# mini_BGM111.net
KiCad netlist of a schematic drawn in EAGLE
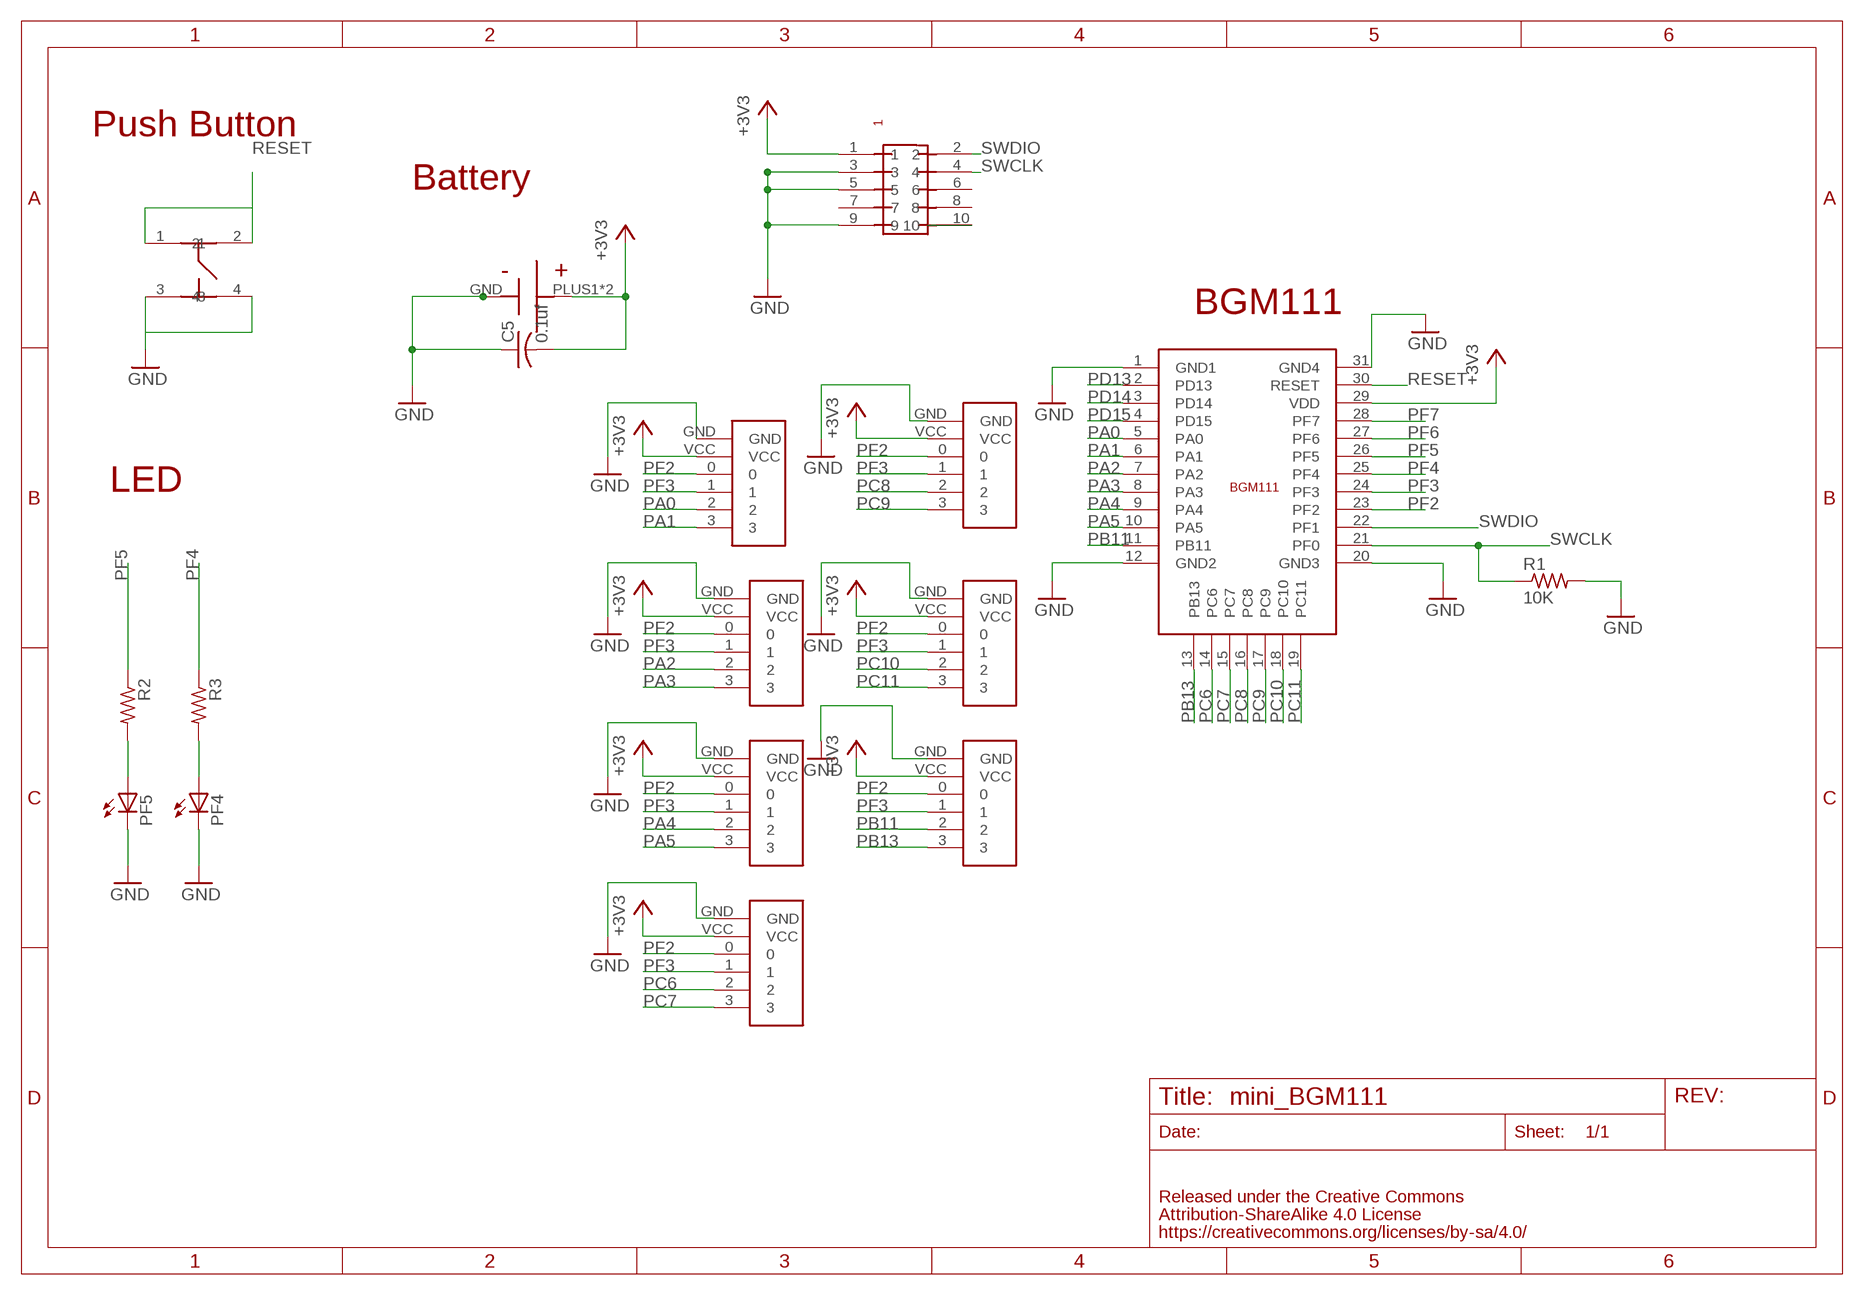
[diagram p0: schematic, sheet 1]

(export (version "E")
  (design (tool "Eeschema 10.0.6"))
  (components
    (comp (ref "C5")
      (value "0.1uf")
      (footprint "eagle-import:C0603")
      (libsource (lib "eagle-import") (part "C-USC0603"))
    )
    (comp (ref "PF4")
      (value "LEDCHIP-LED0603")
      (footprint "eagle-import:CHIP-LED0603")
      (libsource (lib "eagle-import") (part "LEDCHIP-LED0603"))
    )
    (comp (ref "PF5")
      (value "LEDCHIP-LED0603")
      (footprint "eagle-import:CHIP-LED0603")
      (libsource (lib "eagle-import") (part "LEDCHIP-LED0603"))
    )
    (comp (ref "R1")
      (value "10K")
      (footprint "eagle-import:R0603")
      (libsource (lib "eagle-import") (part "R-US_R0603"))
    )
    (comp (ref "R2")
      (value "R-US_R0603")
      (footprint "eagle-import:R0603")
      (libsource (lib "eagle-import") (part "R-US_R0603"))
    )
    (comp (ref "R3")
      (value "R-US_R0603")
      (footprint "eagle-import:R0603")
      (libsource (lib "eagle-import") (part "R-US_R0603"))
    )
    (comp (ref "U$1")
      (value "SILICONLABS-BGM111")
      (footprint "eagle-import:SILICONLABS-BGM111")
      (libsource (lib "eagle-import") (part "SILICONLABS-BGM111"))
    )
    (comp (ref "U$2")
      (value "FABO-PIN-HEADER-2X3-SMD")
      (footprint "eagle-import:FABO-PIN-HEADER-2X3-SMD")
      (libsource (lib "eagle-import") (part "FABO-PIN-HEADER-2X3-SMD"))
    )
    (comp (ref "U$3")
      (value "FABO-PIN-HEADER-2X3-SMD")
      (footprint "eagle-import:FABO-PIN-HEADER-2X3-SMD")
      (libsource (lib "eagle-import") (part "FABO-PIN-HEADER-2X3-SMD"))
    )
    (comp (ref "U$4")
      (value "PIN-HEADER-SMT(1.27MM)2X5")
      (footprint "eagle-import:PIN-HEADER-SMT(1.27MM)2X5")
      (libsource (lib "eagle-import") (part "PIN-HEADER-SMT(1.27MM)2X5"))
    )
    (comp (ref "U$5")
      (value "SWICTH-4P(KMR2)")
      (footprint "eagle-import:SWITCH-4P(KMR2)")
      (libsource (lib "eagle-import") (part "SWICTH-4P(KMR2)"))
    )
    (comp (ref "U$7")
      (value "FABO-PIN-HEADER-2X3-SMD")
      (footprint "eagle-import:FABO-PIN-HEADER-2X3-SMD")
      (libsource (lib "eagle-import") (part "FABO-PIN-HEADER-2X3-SMD"))
    )
    (comp (ref "U$8")
      (value "FABO-PIN-HEADER-2X3-SMD")
      (footprint "eagle-import:FABO-PIN-HEADER-2X3-SMD")
      (libsource (lib "eagle-import") (part "FABO-PIN-HEADER-2X3-SMD"))
    )
    (comp (ref "U$9")
      (value "FABO-PIN-HEADER-2X3-SMD")
      (footprint "eagle-import:FABO-PIN-HEADER-2X3-SMD")
      (libsource (lib "eagle-import") (part "FABO-PIN-HEADER-2X3-SMD"))
    )
    (comp (ref "U$10")
      (value "FABO-PIN-HEADER-2X3-SMD")
      (footprint "eagle-import:FABO-PIN-HEADER-2X3-SMD")
      (libsource (lib "eagle-import") (part "FABO-PIN-HEADER-2X3-SMD"))
    )
    (comp (ref "U$11")
      (value "FABO-PIN-HEADER-2X3-SMD-BOTTOM")
      (footprint "eagle-import:FABO-PIN-HEADER-2X3-SMD-BOTTOM")
      (libsource (lib "eagle-import") (part "FABO-PIN-HEADER-2X3-SMD-BOTTOM"))
    )
    (comp (ref "U$12")
      (value "BRX1-2477")
      (footprint "eagle-import:BRX1-2477")
      (libsource (lib "eagle-import") (part "BRX1-2477"))
    )
  )
  (nets
    (net (code "1") (name "+3V3") (class "Default")
      (node (ref "C5") (pin "2") (pinfunction "2_2") (pintype "passive"))
      (node (ref "U$1") (pin "29") (pinfunction "VDD_29") (pintype "bidirectional"))
      (node (ref "U$10") (pin "VCC") (pinfunction "VCC_VCC") (pintype "bidirectional"))
      (node (ref "U$11") (pin "VCC") (pinfunction "VCC_VCC") (pintype "bidirectional"))
      (node (ref "U$12") (pin "PLUS1") (pinfunction "+_PLUS1") (pintype "bidirectional"))
      (node (ref "U$12") (pin "PLUS2") (pinfunction "+_PLUS2") (pintype "bidirectional"))
      (node (ref "U$2") (pin "VCC") (pinfunction "VCC_VCC") (pintype "bidirectional"))
      (node (ref "U$3") (pin "VCC") (pinfunction "VCC_VCC") (pintype "bidirectional"))
      (node (ref "U$4") (pin "1") (pinfunction "1_1") (pintype "bidirectional"))
      (node (ref "U$7") (pin "VCC") (pinfunction "VCC_VCC") (pintype "bidirectional"))
      (node (ref "U$8") (pin "VCC") (pinfunction "VCC_VCC") (pintype "bidirectional"))
      (node (ref "U$9") (pin "VCC") (pinfunction "VCC_VCC") (pintype "bidirectional"))
    )
    (net (code "2") (name "/PA0") (class "Default")
      (node (ref "U$1") (pin "5") (pinfunction "PA0_5") (pintype "bidirectional"))
      (node (ref "U$3") (pin "2") (pinfunction "2_2") (pintype "bidirectional"))
    )
    (net (code "3") (name "/PA1") (class "Default")
      (node (ref "U$1") (pin "6") (pinfunction "PA1_6") (pintype "bidirectional"))
      (node (ref "U$3") (pin "3") (pinfunction "3_3") (pintype "bidirectional"))
    )
    (net (code "4") (name "/PA2") (class "Default")
      (node (ref "U$1") (pin "7") (pinfunction "PA2_7") (pintype "bidirectional"))
      (node (ref "U$7") (pin "2") (pinfunction "2_2") (pintype "bidirectional"))
    )
    (net (code "5") (name "/PA3") (class "Default")
      (node (ref "U$1") (pin "8") (pinfunction "PA3_8") (pintype "bidirectional"))
      (node (ref "U$7") (pin "3") (pinfunction "3_3") (pintype "bidirectional"))
    )
    (net (code "6") (name "/PA4") (class "Default")
      (node (ref "U$1") (pin "9") (pinfunction "PA4_9") (pintype "bidirectional"))
      (node (ref "U$8") (pin "2") (pinfunction "2_2") (pintype "bidirectional"))
    )
    (net (code "7") (name "/PA5") (class "Default")
      (node (ref "U$1") (pin "10") (pinfunction "PA5_10") (pintype "bidirectional"))
      (node (ref "U$8") (pin "3") (pinfunction "3_3") (pintype "bidirectional"))
    )
    (net (code "8") (name "/PB11") (class "Default")
      (node (ref "U$1") (pin "11") (pinfunction "PB11_11") (pintype "bidirectional"))
      (node (ref "U$11") (pin "2") (pinfunction "2_2") (pintype "bidirectional"))
    )
    (net (code "9") (name "/PB13") (class "Default")
      (node (ref "U$1") (pin "13") (pinfunction "PB13_13") (pintype "bidirectional"))
      (node (ref "U$11") (pin "3") (pinfunction "3_3") (pintype "bidirectional"))
    )
    (net (code "10") (name "/PC6") (class "Default")
      (node (ref "U$1") (pin "14") (pinfunction "PC6_14") (pintype "bidirectional"))
      (node (ref "U$2") (pin "2") (pinfunction "2_2") (pintype "bidirectional"))
    )
    (net (code "11") (name "/PC7") (class "Default")
      (node (ref "U$1") (pin "15") (pinfunction "PC7_15") (pintype "bidirectional"))
      (node (ref "U$2") (pin "3") (pinfunction "3_3") (pintype "bidirectional"))
    )
    (net (code "12") (name "/PC8") (class "Default")
      (node (ref "U$1") (pin "16") (pinfunction "PC8_16") (pintype "bidirectional"))
      (node (ref "U$9") (pin "2") (pinfunction "2_2") (pintype "bidirectional"))
    )
    (net (code "13") (name "/PC9") (class "Default")
      (node (ref "U$1") (pin "17") (pinfunction "PC9_17") (pintype "bidirectional"))
      (node (ref "U$9") (pin "3") (pinfunction "3_3") (pintype "bidirectional"))
    )
    (net (code "14") (name "/PC10") (class "Default")
      (node (ref "U$1") (pin "18") (pinfunction "PC10_18") (pintype "bidirectional"))
      (node (ref "U$10") (pin "2") (pinfunction "2_2") (pintype "bidirectional"))
    )
    (net (code "15") (name "/PC11") (class "Default")
      (node (ref "U$1") (pin "19") (pinfunction "PC11_19") (pintype "bidirectional"))
      (node (ref "U$10") (pin "3") (pinfunction "3_3") (pintype "bidirectional"))
    )
    (net (code "16") (name "/PD13") (class "Default")
      (node (ref "U$1") (pin "2") (pinfunction "PD13_2") (pintype "bidirectional"))
    )
    (net (code "17") (name "/PD14") (class "Default")
      (node (ref "U$1") (pin "3") (pinfunction "PD14_3") (pintype "bidirectional"))
    )
    (net (code "18") (name "/PD15") (class "Default")
      (node (ref "U$1") (pin "4") (pinfunction "PD15_4") (pintype "bidirectional"))
    )
    (net (code "19") (name "/PF2") (class "Default")
      (node (ref "U$1") (pin "23") (pinfunction "PF2_23") (pintype "bidirectional"))
      (node (ref "U$10") (pin "0") (pinfunction "0_0") (pintype "bidirectional"))
      (node (ref "U$11") (pin "0") (pinfunction "0_0") (pintype "bidirectional"))
      (node (ref "U$2") (pin "0") (pinfunction "0_0") (pintype "bidirectional"))
      (node (ref "U$3") (pin "0") (pinfunction "0_0") (pintype "bidirectional"))
      (node (ref "U$7") (pin "0") (pinfunction "0_0") (pintype "bidirectional"))
      (node (ref "U$8") (pin "0") (pinfunction "0_0") (pintype "bidirectional"))
      (node (ref "U$9") (pin "0") (pinfunction "0_0") (pintype "bidirectional"))
    )
    (net (code "20") (name "/PF3") (class "Default")
      (node (ref "U$1") (pin "24") (pinfunction "PF3_24") (pintype "bidirectional"))
      (node (ref "U$10") (pin "1") (pinfunction "1_1") (pintype "bidirectional"))
      (node (ref "U$11") (pin "1") (pinfunction "1_1") (pintype "bidirectional"))
      (node (ref "U$2") (pin "1") (pinfunction "1_1") (pintype "bidirectional"))
      (node (ref "U$3") (pin "1") (pinfunction "1_1") (pintype "bidirectional"))
      (node (ref "U$7") (pin "1") (pinfunction "1_1") (pintype "bidirectional"))
      (node (ref "U$8") (pin "1") (pinfunction "1_1") (pintype "bidirectional"))
      (node (ref "U$9") (pin "1") (pinfunction "1_1") (pintype "bidirectional"))
    )
    (net (code "21") (name "/PF4") (class "Default")
      (node (ref "R3") (pin "1") (pinfunction "1_1") (pintype "passive"))
      (node (ref "U$1") (pin "25") (pinfunction "PF4_25") (pintype "bidirectional"))
    )
    (net (code "22") (name "/PF5") (class "Default")
      (node (ref "R2") (pin "1") (pinfunction "1_1") (pintype "passive"))
      (node (ref "U$1") (pin "26") (pinfunction "PF5_26") (pintype "bidirectional"))
    )
    (net (code "23") (name "/PF6") (class "Default")
      (node (ref "U$1") (pin "27") (pinfunction "PF6_27") (pintype "bidirectional"))
    )
    (net (code "24") (name "/PF7") (class "Default")
      (node (ref "U$1") (pin "28") (pinfunction "PF7_28") (pintype "bidirectional"))
    )
    (net (code "25") (name "/RESET") (class "Default")
      (node (ref "U$1") (pin "30") (pinfunction "RESET_30") (pintype "bidirectional"))
      (node (ref "U$5") (pin "1") (pinfunction "1_1") (pintype "bidirectional"))
      (node (ref "U$5") (pin "2") (pinfunction "2_2") (pintype "bidirectional"))
    )
    (net (code "26") (name "/SWCLK") (class "Default")
      (node (ref "R1") (pin "1") (pinfunction "1_1") (pintype "passive"))
      (node (ref "U$1") (pin "21") (pinfunction "PF0_21") (pintype "bidirectional"))
      (node (ref "U$4") (pin "4") (pinfunction "4_4") (pintype "bidirectional"))
    )
    (net (code "27") (name "/SWDIO") (class "Default")
      (node (ref "U$1") (pin "22") (pinfunction "PF1_22") (pintype "bidirectional"))
      (node (ref "U$4") (pin "2") (pinfunction "2_2") (pintype "bidirectional"))
    )
    (net (code "28") (name "GND") (class "Default")
      (node (ref "C5") (pin "1") (pinfunction "1_1") (pintype "passive"))
      (node (ref "PF4") (pin "C") (pinfunction "C_C") (pintype "passive"))
      (node (ref "PF5") (pin "C") (pinfunction "C_C") (pintype "passive"))
      (node (ref "R1") (pin "2") (pinfunction "2_2") (pintype "passive"))
      (node (ref "U$1") (pin "1") (pinfunction "GND1_1") (pintype "bidirectional"))
      (node (ref "U$1") (pin "12") (pinfunction "GND2_12") (pintype "bidirectional"))
      (node (ref "U$1") (pin "20") (pinfunction "GND3_20") (pintype "bidirectional"))
      (node (ref "U$1") (pin "31") (pinfunction "GND4_31") (pintype "bidirectional"))
      (node (ref "U$10") (pin "GND") (pinfunction "GND_GND") (pintype "bidirectional"))
      (node (ref "U$11") (pin "GND") (pinfunction "GND_GND") (pintype "bidirectional"))
      (node (ref "U$12") (pin "GND") (pinfunction "-_GND") (pintype "bidirectional"))
      (node (ref "U$2") (pin "GND") (pinfunction "GND_GND") (pintype "bidirectional"))
      (node (ref "U$3") (pin "GND") (pinfunction "GND_GND") (pintype "bidirectional"))
      (node (ref "U$4") (pin "3") (pinfunction "3_3") (pintype "bidirectional"))
      (node (ref "U$4") (pin "5") (pinfunction "5_5") (pintype "bidirectional"))
      (node (ref "U$4") (pin "9") (pinfunction "9_9") (pintype "bidirectional"))
      (node (ref "U$5") (pin "3") (pinfunction "3_3") (pintype "bidirectional"))
      (node (ref "U$5") (pin "4") (pinfunction "4_4") (pintype "bidirectional"))
      (node (ref "U$7") (pin "GND") (pinfunction "GND_GND") (pintype "bidirectional"))
      (node (ref "U$8") (pin "GND") (pinfunction "GND_GND") (pintype "bidirectional"))
      (node (ref "U$9") (pin "GND") (pinfunction "GND_GND") (pintype "bidirectional"))
    )
    (net (code "29") (name "Net-(PF4-PadA)") (class "Default")
      (node (ref "PF4") (pin "A") (pinfunction "A_A") (pintype "passive"))
      (node (ref "R3") (pin "2") (pinfunction "2_2") (pintype "passive"))
    )
    (net (code "30") (name "Net-(PF5-PadA)") (class "Default")
      (node (ref "PF5") (pin "A") (pinfunction "A_A") (pintype "passive"))
      (node (ref "R2") (pin "2") (pinfunction "2_2") (pintype "passive"))
    )
    (net (code "31") (name "unconnected-(U$4-Pad6)") (class "Default")
      (node (ref "U$4") (pin "6") (pinfunction "6_6") (pintype "bidirectional"))
    )
    (net (code "32") (name "unconnected-(U$4-Pad7)") (class "Default")
      (node (ref "U$4") (pin "7") (pinfunction "7_7") (pintype "bidirectional"))
    )
    (net (code "33") (name "unconnected-(U$4-Pad8)") (class "Default")
      (node (ref "U$4") (pin "8") (pinfunction "8_8") (pintype "bidirectional"))
    )
    (net (code "34") (name "unconnected-(U$4-Pad10)") (class "Default")
      (node (ref "U$4") (pin "10") (pinfunction "10_10") (pintype "bidirectional"))
    )
  )
)
